# Main_Buck.net
KiCad netlist of a schematic drawn in Altium Designer
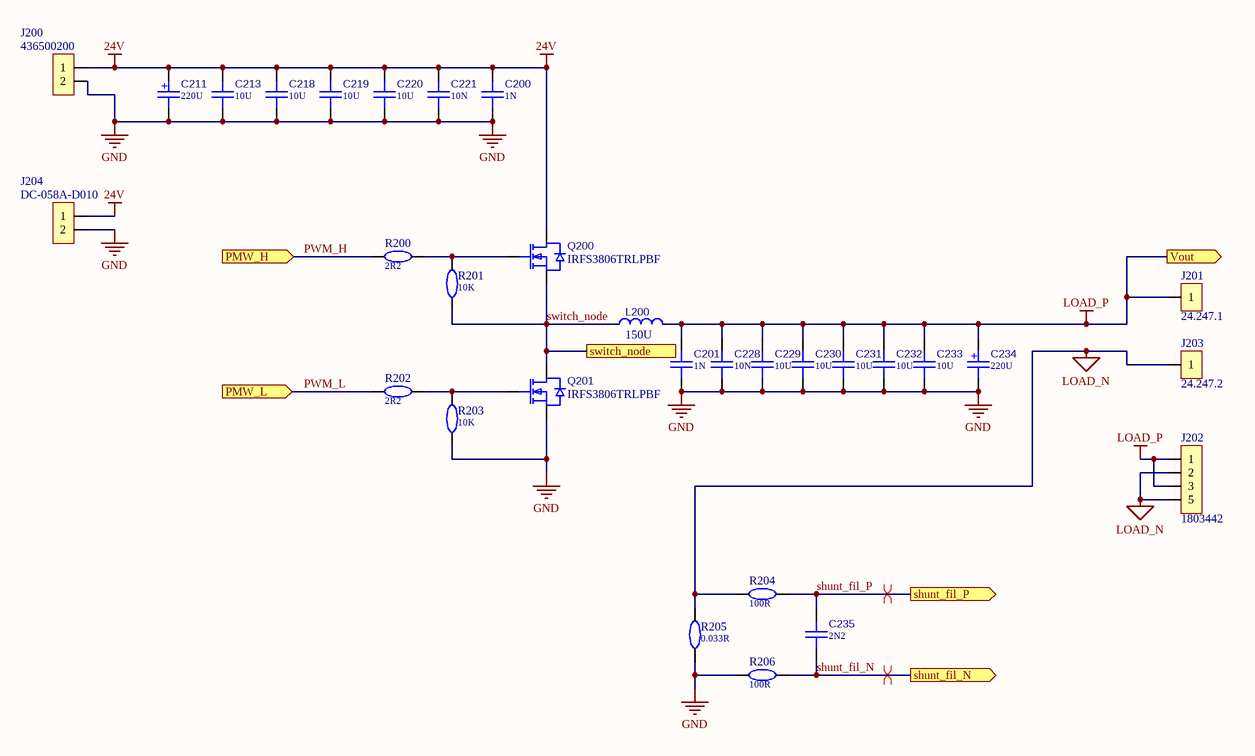
[diagram p0: Main_Buck.SchDoc]

(export (version "E")
  (design (tool "Eeschema 10.0.6"))
  (components
    (comp (ref "C200")
      (value "1N")
      (footprint "CAP_0402")
      (description "CAP 1N 0402 X7R 50V 10%")
      (fields (field (name "PART NUMBER") "UMF105B7102KVHF") (field (name "Comment") "CAPACITOR"))
      (libsource (lib "Altium_Library") (part "CAPACITOR"))
    )
    (comp (ref "C201")
      (value "1N")
      (footprint "CAP_0402")
      (description "CAP 1N 0402 X7R 50V 10%")
      (fields (field (name "PART NUMBER") "UMF105B7102KVHF") (field (name "Comment") "CAPACITOR"))
      (libsource (lib "Altium_Library") (part "CAPACITOR"))
    )
    (comp (ref "C211")
      (value "220U")
      (footprint "CAP_SMD_UUD1H221MNL1GS")
      (description "CAP 220U SMD_D10mm_L10mm ELEC 50V 20%")
      (fields (field (name "PART NUMBER") "UUD1H221MNL1GS") (field (name "Comment") "CAPACITOR_POLARIZED"))
      (libsource (lib "Altium_Library") (part "CAPACITOR_POLARIZED"))
    )
    (comp (ref "C213")
      (value "10U")
      (footprint "CAP_1210")
      (description "CAP 10U 1210 X7R 50V 10%")
      (fields (field (name "PART NUMBER") "UMK325AB7106KM-T") (field (name "Comment") "CAPACITOR"))
      (libsource (lib "Altium_Library") (part "CAPACITOR"))
    )
    (comp (ref "C218")
      (value "10U")
      (footprint "CAP_1210")
      (description "CAP 10U 1210 X7R 50V 10%")
      (fields (field (name "PART NUMBER") "UMK325AB7106KM-T") (field (name "Comment") "CAPACITOR"))
      (libsource (lib "Altium_Library") (part "CAPACITOR"))
    )
    (comp (ref "C219")
      (value "10U")
      (footprint "CAP_1210")
      (description "CAP 10U 1210 X7R 50V 10%")
      (fields (field (name "PART NUMBER") "UMK325AB7106KM-T") (field (name "Comment") "CAPACITOR"))
      (libsource (lib "Altium_Library") (part "CAPACITOR"))
    )
    (comp (ref "C220")
      (value "10U")
      (footprint "CAP_1210")
      (description "CAP 10U 1210 X7R 50V 10%")
      (fields (field (name "PART NUMBER") "UMK325AB7106KM-T") (field (name "Comment") "CAPACITOR"))
      (libsource (lib "Altium_Library") (part "CAPACITOR"))
    )
    (comp (ref "C221")
      (value "10N")
      (footprint "CAP_0402")
      (description "CAP 10N 0402 X7R 50V 10%")
      (fields (field (name "PART NUMBER") "UMF105B7103KVHF") (field (name "Comment") "CAPACITOR"))
      (libsource (lib "Altium_Library") (part "CAPACITOR"))
    )
    (comp (ref "C228")
      (value "10N")
      (footprint "CAP_0402")
      (description "CAP 10N 0402 X7R 50V 10%")
      (fields (field (name "PART NUMBER") "UMF105B7103KVHF") (field (name "Comment") "CAPACITOR"))
      (libsource (lib "Altium_Library") (part "CAPACITOR"))
    )
    (comp (ref "C229")
      (value "10U")
      (footprint "CAP_1210")
      (description "CAP 10U 1210 X7R 50V 10%")
      (fields (field (name "PART NUMBER") "UMK325AB7106KM-T") (field (name "Comment") "CAPACITOR"))
      (libsource (lib "Altium_Library") (part "CAPACITOR"))
    )
    (comp (ref "C230")
      (value "10U")
      (footprint "CAP_1210")
      (description "CAP 10U 1210 X7R 50V 10%")
      (fields (field (name "PART NUMBER") "UMK325AB7106KM-T") (field (name "Comment") "CAPACITOR"))
      (libsource (lib "Altium_Library") (part "CAPACITOR"))
    )
    (comp (ref "C231")
      (value "10U")
      (footprint "CAP_1210")
      (description "CAP 10U 1210 X7R 50V 10%")
      (fields (field (name "PART NUMBER") "UMK325AB7106KM-T") (field (name "Comment") "CAPACITOR"))
      (libsource (lib "Altium_Library") (part "CAPACITOR"))
    )
    (comp (ref "C232")
      (value "10U")
      (footprint "CAP_1210")
      (description "CAP 10U 1210 X7R 50V 10%")
      (fields (field (name "PART NUMBER") "UMK325AB7106KM-T") (field (name "Comment") "CAPACITOR"))
      (libsource (lib "Altium_Library") (part "CAPACITOR"))
    )
    (comp (ref "C233")
      (value "10U")
      (footprint "CAP_1210")
      (description "CAP 10U 1210 X7R 50V 10%")
      (fields (field (name "PART NUMBER") "UMK325AB7106KM-T") (field (name "Comment") "CAPACITOR"))
      (libsource (lib "Altium_Library") (part "CAPACITOR"))
    )
    (comp (ref "C234")
      (value "220U")
      (footprint "CAP_SMD_UUD1H221MNL1GS")
      (description "CAP 220U SMD_D10mm_L10mm ELEC 50V 20%")
      (fields (field (name "PART NUMBER") "UUD1H221MNL1GS") (field (name "Comment") "CAPACITOR_POLARIZED"))
      (libsource (lib "Altium_Library") (part "CAPACITOR_POLARIZED"))
    )
    (comp (ref "C235")
      (value "2N2")
      (footprint "CAP_0603")
      (description "CAP 2N2 0603 NPO 250V 5%")
      (fields (field (name "PART NUMBER") "C1608C0G2E222JT000N") (field (name "Comment") "CAPACITOR"))
      (libsource (lib "Altium_Library") (part "CAPACITOR"))
    )
    (comp (ref "J200")
      (value "436500200")
      (footprint "CON_436500200")
      (description "RECEP 436500200 TH 3mm HORIZ")
      (fields (field (name "VOLTAGE") "600V") (field (name "Comment") "JACK_2P"))
      (libsource (lib "Altium_Library") (part "JACK_2P"))
    )
    (comp (ref "J201")
      (value "24.247.1")
      (footprint "BANANA_JACK_RED_24.247.1")
      (description "JACK  24.247.1 TH 4mm  VERT RED")
      (fields (field (name "VOLTAGE") "60V") (field (name "Comment") "JACK_1P"))
      (libsource (lib "Altium_Library") (part "JACK_1P"))
    )
    (comp (ref "J202")
      (value "1803442")
      (footprint "CON_1803442")
      (description "RECEP 1803442 TH 3.81mm HORIZ")
      (fields (field (name "VOLTAGE") "160V") (field (name "Comment") "JACK_4P"))
      (libsource (lib "Altium_Library") (part "JACK_4P"))
    )
    (comp (ref "J203")
      (value "24.247.2")
      (footprint "BANANA_JACK_BLACK_24.247.2")
      (description "JACK  24.247.2 TH 4mm  VERT BLACK")
      (fields (field (name "VOLTAGE") "60V") (field (name "Comment") "JACK_1P"))
      (libsource (lib "Altium_Library") (part "JACK_1P"))
    )
    (comp (ref "J204")
      (value "DC-058A-D010")
      (footprint "CON_DC-058A-D010")
      (description "JACK \nDC-058A-D010 TH  HORIZ")
      (fields (field (name "VOLTAGE") "12V") (field (name "Comment") "JACK_2P"))
      (libsource (lib "Altium_Library") (part "JACK_2P"))
    )
    (comp (ref "L200")
      (value "150U")
      (footprint "IND_74437429203151")
      (description "IND 150U SMD_W25mm_L28mm 8.4A 7.8A")
      (fields (field (name "PART NUMBER") "74437429203151") (field (name "Comment") "INDUCTOR"))
      (libsource (lib "Altium_Library") (part "INDUCTOR"))
    )
    (comp (ref "Q200")
      (value "IRFS3806TRLPBF")
      (footprint "D2PAK")
      (description "NFET IRFS3806TRLPBF D2PAK 60V 43A 15.8mΩ")
      (fields (field (name "VOLTAGE") "60V") (field (name "Comment") "MOSFET_NCHANNEL"))
      (libsource (lib "Altium_Library") (part "MOSFET_NCHANNEL"))
    )
    (comp (ref "Q201")
      (value "IRFS3806TRLPBF")
      (footprint "D2PAK")
      (description "NFET IRFS3806TRLPBF D2PAK 60V 43A 15.8mΩ")
      (fields (field (name "VOLTAGE") "60V") (field (name "Comment") "MOSFET_NCHANNEL"))
      (libsource (lib "Altium_Library") (part "MOSFET_NCHANNEL"))
    )
    (comp (ref "R200")
      (value "2R2")
      (footprint "RES_0603")
      (description "RES 2R2 0603 0.1W 5% 75V")
      (fields (field (name "PART NUMBER") "0603WAJ022JT5E") (field (name "Comment") "RESISTOR"))
      (libsource (lib "Altium_Library") (part "RESISTOR"))
    )
    (comp (ref "R201")
      (value "10K")
      (footprint "RES_0603")
      (description "RES 10K 0603 0.1W 0.1% 75V")
      (fields (field (name "PART NUMBER") "ARG03BTC1002") (field (name "Comment") "RESISTOR"))
      (libsource (lib "Altium_Library") (part "RESISTOR"))
    )
    (comp (ref "R202")
      (value "2R2")
      (footprint "RES_0603")
      (description "RES 2R2 0603 0.1W 5% 75V")
      (fields (field (name "PART NUMBER") "0603WAJ022JT5E") (field (name "Comment") "RESISTOR"))
      (libsource (lib "Altium_Library") (part "RESISTOR"))
    )
    (comp (ref "R203")
      (value "10K")
      (footprint "RES_0603")
      (description "RES 10K 0603 0.1W 0.1% 75V")
      (fields (field (name "PART NUMBER") "ARG03BTC1002") (field (name "Comment") "RESISTOR"))
      (libsource (lib "Altium_Library") (part "RESISTOR"))
    )
    (comp (ref "R204")
      (value "100R")
      (footprint "RES_0603")
      (description "RES 100R 00603 0.1W 0.25% 75V")
      (fields (field (name "PART NUMBER") "RT0603CRE07100RL") (field (name "Comment") "RESISTOR"))
      (libsource (lib "Altium_Library") (part "RESISTOR"))
    )
    (comp (ref "R205")
      (value "0.033R")
      (footprint "RES_1210")
      (description "RES 0.033R 1210 1% 0.5W 200V")
      (fields (field (name "PART NUMBER") "RTT12R033FTP") (field (name "Comment") "RESISTOR"))
      (libsource (lib "Altium_Library") (part "RESISTOR"))
    )
    (comp (ref "R206")
      (value "100R")
      (footprint "RES_0603")
      (description "RES 100R 00603 0.1W 0.25% 75V")
      (fields (field (name "PART NUMBER") "RT0603CRE07100RL") (field (name "Comment") "RESISTOR"))
      (libsource (lib "Altium_Library") (part "RESISTOR"))
    )
  )
  (nets
    (net (code "1") (name "/PWM_H") (class "Default")
      (node (ref "R200") (pin "1") (pinfunction "1_1") (pintype "passive"))
    )
    (net (code "2") (name "/PWM_L") (class "Default")
      (node (ref "R202") (pin "1") (pinfunction "1_1") (pintype "passive"))
    )
    (net (code "3") (name "/shunt_fil_N") (class "Default")
      (node (ref "C235") (pin "1") (pinfunction "1_1") (pintype "passive"))
      (node (ref "R206") (pin "2") (pinfunction "2_2") (pintype "passive"))
    )
    (net (code "4") (name "/shunt_fil_P") (class "Default")
      (node (ref "C235") (pin "2") (pinfunction "2_2") (pintype "passive"))
      (node (ref "R204") (pin "2") (pinfunction "2_2") (pintype "passive"))
    )
    (net (code "5") (name "/switch_node") (class "Default")
      (node (ref "L200") (pin "1") (pinfunction "1_1") (pintype "passive"))
      (node (ref "Q200") (pin "3") (pinfunction "S_3") (pintype "passive"))
      (node (ref "Q201") (pin "4") (pinfunction "D_4") (pintype "passive"))
      (node (ref "R201") (pin "1") (pinfunction "1_1") (pintype "passive"))
    )
    (net (code "6") (name "24V") (class "Default")
      (node (ref "C200") (pin "2") (pinfunction "2_2") (pintype "passive"))
      (node (ref "C211") (pin "1") (pinfunction "1_1") (pintype "passive"))
      (node (ref "C213") (pin "1") (pinfunction "1_1") (pintype "passive"))
      (node (ref "C218") (pin "1") (pinfunction "1_1") (pintype "passive"))
      (node (ref "C219") (pin "1") (pinfunction "1_1") (pintype "passive"))
      (node (ref "C220") (pin "1") (pinfunction "1_1") (pintype "passive"))
      (node (ref "C221") (pin "2") (pinfunction "2_2") (pintype "passive"))
      (node (ref "J200") (pin "1") (pinfunction "1_1") (pintype "passive"))
      (node (ref "J204") (pin "1") (pinfunction "1_1") (pintype "passive"))
      (node (ref "Q200") (pin "4") (pinfunction "D_4") (pintype "passive"))
    )
    (net (code "7") (name "GND") (class "Default")
      (node (ref "C200") (pin "1") (pinfunction "1_1") (pintype "passive"))
      (node (ref "C201") (pin "2") (pinfunction "2_2") (pintype "passive"))
      (node (ref "C211") (pin "2") (pinfunction "2_2") (pintype "passive"))
      (node (ref "C213") (pin "2") (pinfunction "2_2") (pintype "passive"))
      (node (ref "C218") (pin "2") (pinfunction "2_2") (pintype "passive"))
      (node (ref "C219") (pin "2") (pinfunction "2_2") (pintype "passive"))
      (node (ref "C220") (pin "2") (pinfunction "2_2") (pintype "passive"))
      (node (ref "C221") (pin "1") (pinfunction "1_1") (pintype "passive"))
      (node (ref "C228") (pin "1") (pinfunction "1_1") (pintype "passive"))
      (node (ref "C229") (pin "2") (pinfunction "2_2") (pintype "passive"))
      (node (ref "C230") (pin "2") (pinfunction "2_2") (pintype "passive"))
      (node (ref "C231") (pin "2") (pinfunction "2_2") (pintype "passive"))
      (node (ref "C232") (pin "2") (pinfunction "2_2") (pintype "passive"))
      (node (ref "C233") (pin "2") (pinfunction "2_2") (pintype "passive"))
      (node (ref "C234") (pin "2") (pinfunction "2_2") (pintype "passive"))
      (node (ref "J200") (pin "2") (pinfunction "2_2") (pintype "passive"))
      (node (ref "J204") (pin "2") (pinfunction "2_2") (pintype "passive"))
      (node (ref "Q201") (pin "3") (pinfunction "S_3") (pintype "passive"))
      (node (ref "R203") (pin "1") (pinfunction "1_1") (pintype "passive"))
      (node (ref "R205") (pin "1") (pinfunction "1_1") (pintype "passive"))
      (node (ref "R206") (pin "1") (pinfunction "1_1") (pintype "passive"))
    )
    (net (code "8") (name "LOAD_N") (class "Default")
      (node (ref "J202") (pin "2") (pinfunction "2_2") (pintype "passive"))
      (node (ref "J202") (pin "4") (pinfunction "5_4") (pintype "passive"))
      (node (ref "J203") (pin "1") (pinfunction "1_1") (pintype "passive"))
      (node (ref "R204") (pin "1") (pinfunction "1_1") (pintype "passive"))
      (node (ref "R205") (pin "2") (pinfunction "2_2") (pintype "passive"))
    )
    (net (code "9") (name "LOAD_P") (class "Default")
      (node (ref "C201") (pin "1") (pinfunction "1_1") (pintype "passive"))
      (node (ref "C228") (pin "2") (pinfunction "2_2") (pintype "passive"))
      (node (ref "C229") (pin "1") (pinfunction "1_1") (pintype "passive"))
      (node (ref "C230") (pin "1") (pinfunction "1_1") (pintype "passive"))
      (node (ref "C231") (pin "1") (pinfunction "1_1") (pintype "passive"))
      (node (ref "C232") (pin "1") (pinfunction "1_1") (pintype "passive"))
      (node (ref "C233") (pin "1") (pinfunction "1_1") (pintype "passive"))
      (node (ref "C234") (pin "1") (pinfunction "1_1") (pintype "passive"))
      (node (ref "J201") (pin "1") (pinfunction "1_1") (pintype "passive"))
      (node (ref "J202") (pin "1") (pinfunction "1_1") (pintype "passive"))
      (node (ref "J202") (pin "3") (pinfunction "3_3") (pintype "passive"))
      (node (ref "L200") (pin "2") (pinfunction "2_2") (pintype "passive"))
    )
    (net (code "10") (name "Net-(Q200-G)") (class "Default")
      (node (ref "Q200") (pin "1") (pinfunction "G_1") (pintype "passive"))
      (node (ref "R200") (pin "2") (pinfunction "2_2") (pintype "passive"))
      (node (ref "R201") (pin "2") (pinfunction "2_2") (pintype "passive"))
    )
    (net (code "11") (name "Net-(Q201-G)") (class "Default")
      (node (ref "Q201") (pin "1") (pinfunction "G_1") (pintype "passive"))
      (node (ref "R202") (pin "2") (pinfunction "2_2") (pintype "passive"))
      (node (ref "R203") (pin "2") (pinfunction "2_2") (pintype "passive"))
    )
  )
)
